# IOB-Inputs.net
KiCad netlist of a schematic drawn in EAGLE
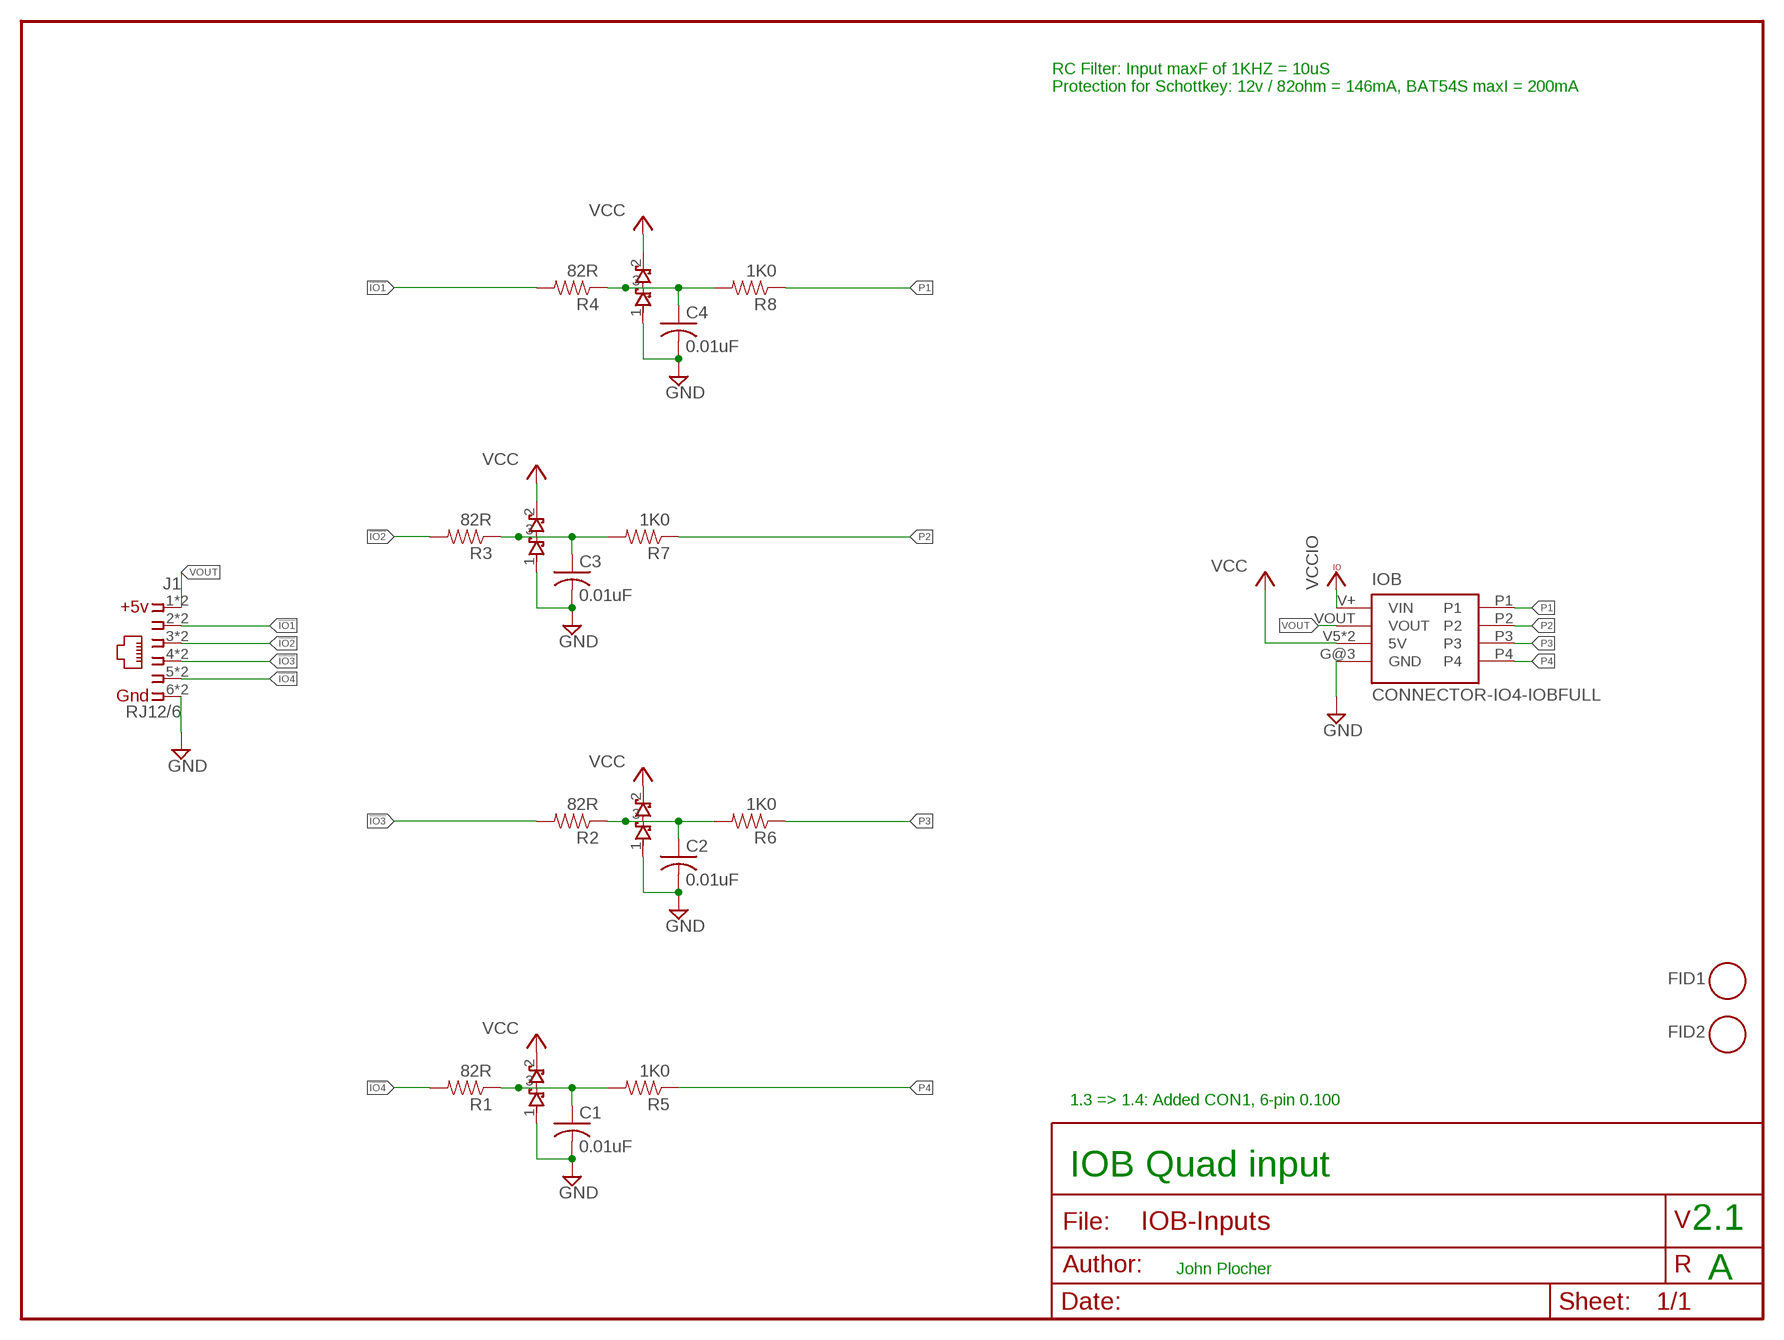
[diagram p0: schematic, sheet 1]

(export (version "E")
  (design (tool "Eeschema 10.0.6"))
  (components
    (comp (ref "C1")
      (value "0.01uF")
      (footprint "eagle-import:0603-CAP")
      (libsource (lib "eagle-import") (part "CAP0603"))
    )
    (comp (ref "C2")
      (value "0.01uF")
      (footprint "eagle-import:0603-CAP")
      (libsource (lib "eagle-import") (part "CAP0603"))
    )
    (comp (ref "C3")
      (value "0.01uF")
      (footprint "eagle-import:0603-CAP")
      (libsource (lib "eagle-import") (part "CAP0603"))
    )
    (comp (ref "C4")
      (value "0.01uF")
      (footprint "eagle-import:0603-CAP")
      (libsource (lib "eagle-import") (part "CAP0603"))
    )
    (comp (ref "D1")
      (value "BAT54S")
      (footprint "eagle-import:SOT23")
      (libsource (lib "eagle-import") (part "DIODE-BAT54S23"))
    )
    (comp (ref "D2")
      (value "BAT54S")
      (footprint "eagle-import:SOT23")
      (libsource (lib "eagle-import") (part "DIODE-BAT54S23"))
    )
    (comp (ref "D3")
      (value "BAT54S")
      (footprint "eagle-import:SOT23")
      (libsource (lib "eagle-import") (part "DIODE-BAT54S23"))
    )
    (comp (ref "D4")
      (value "BAT54S")
      (footprint "eagle-import:SOT23")
      (libsource (lib "eagle-import") (part "DIODE-BAT54S23"))
    )
    (comp (ref "FID1")
      (value "FIDUCIAL")
      (footprint "eagle-import:FIDUCIAL_1MM")
      (libsource (lib "eagle-import") (part "FIDUCIAL"))
    )
    (comp (ref "FID2")
      (value "FIDUCIAL")
      (footprint "eagle-import:FIDUCIAL_1MM")
      (libsource (lib "eagle-import") (part "FIDUCIAL"))
    )
    (comp (ref "IOB")
      (value "CONNECTOR-IO4-IOBFULL")
      (footprint "eagle-import:IO4-IOB")
      (libsource (lib "eagle-import") (part "CONNECTOR-IO4-IOBFULL"))
    )
    (comp (ref "J1")
      (value "RJ12/6")
      (footprint "eagle-import:RJ24-INVERTED-PINS")
      (libsource (lib "eagle-import") (part "CONNECTOR-IO4IPINS"))
    )
    (comp (ref "R1")
      (value "82R")
      (footprint "eagle-import:0805-RES")
      (libsource (lib "eagle-import") (part "R0805-RES"))
    )
    (comp (ref "R2")
      (value "82R")
      (footprint "eagle-import:0805-RES")
      (libsource (lib "eagle-import") (part "R0805-RES"))
    )
    (comp (ref "R3")
      (value "82R")
      (footprint "eagle-import:0805-RES")
      (libsource (lib "eagle-import") (part "R0805-RES"))
    )
    (comp (ref "R4")
      (value "82R")
      (footprint "eagle-import:0805-RES")
      (libsource (lib "eagle-import") (part "R0805-RES"))
    )
    (comp (ref "R5")
      (value "1K0")
      (footprint "eagle-import:0603-RES")
      (libsource (lib "eagle-import") (part "R0603-RES"))
    )
    (comp (ref "R6")
      (value "1K0")
      (footprint "eagle-import:0603-RES")
      (libsource (lib "eagle-import") (part "R0603-RES"))
    )
    (comp (ref "R7")
      (value "1K0")
      (footprint "eagle-import:0603-RES")
      (libsource (lib "eagle-import") (part "R0603-RES"))
    )
    (comp (ref "R8")
      (value "1K0")
      (footprint "eagle-import:0603-RES")
      (libsource (lib "eagle-import") (part "R0603-RES"))
    )
  )
  (nets
    (net (code "1") (name "/~{IO1}") (class "Default")
      (node (ref "J1") (pin "2") (pinfunction "2_2") (pintype "passive"))
      (node (ref "J1") (pin "2@1") (pinfunction "2_2@1") (pintype "passive"))
      (node (ref "R4") (pin "2") (pinfunction "2_2") (pintype "passive"))
    )
    (net (code "2") (name "/~{IO2}") (class "Default")
      (node (ref "J1") (pin "3") (pinfunction "3_3") (pintype "passive"))
      (node (ref "J1") (pin "3@1") (pinfunction "3_3@1") (pintype "passive"))
      (node (ref "R3") (pin "2") (pinfunction "2_2") (pintype "passive"))
    )
    (net (code "3") (name "/~{IO3}") (class "Default")
      (node (ref "J1") (pin "4") (pinfunction "4_4") (pintype "passive"))
      (node (ref "J1") (pin "4@1") (pinfunction "4_4@1") (pintype "passive"))
      (node (ref "R2") (pin "2") (pinfunction "2_2") (pintype "passive"))
    )
    (net (code "4") (name "/~{IO4}") (class "Default")
      (node (ref "J1") (pin "5") (pinfunction "5_5") (pintype "passive"))
      (node (ref "J1") (pin "5@1") (pinfunction "5_5@1") (pintype "passive"))
      (node (ref "R1") (pin "2") (pinfunction "2_2") (pintype "passive"))
    )
    (net (code "5") (name "GND") (class "Default")
      (node (ref "C1") (pin "2") (pinfunction "2_2") (pintype "passive"))
      (node (ref "C2") (pin "2") (pinfunction "2_2") (pintype "passive"))
      (node (ref "C3") (pin "2") (pinfunction "2_2") (pintype "passive"))
      (node (ref "C4") (pin "2") (pinfunction "2_2") (pintype "passive"))
      (node (ref "D1") (pin "1") (pinfunction "A1_1") (pintype "bidirectional"))
      (node (ref "D2") (pin "1") (pinfunction "A1_1") (pintype "bidirectional"))
      (node (ref "D3") (pin "1") (pinfunction "A1_1") (pintype "bidirectional"))
      (node (ref "D4") (pin "1") (pinfunction "A1_1") (pintype "bidirectional"))
      (node (ref "IOB") (pin "G@3") (pinfunction "GND_G@3") (pintype "power_in"))
      (node (ref "J1") (pin "6") (pinfunction "6_6") (pintype "power_in"))
      (node (ref "J1") (pin "6@1") (pinfunction "6_6@1") (pintype "power_in"))
    )
    (net (code "6") (name "Net-(D1-COM)") (class "Default")
      (node (ref "C1") (pin "1") (pinfunction "1_1") (pintype "passive"))
      (node (ref "D1") (pin "3") (pinfunction "COM_3") (pintype "bidirectional"))
      (node (ref "R1") (pin "1") (pinfunction "1_1") (pintype "passive"))
      (node (ref "R5") (pin "2") (pinfunction "2_2") (pintype "passive"))
    )
    (net (code "7") (name "Net-(D2-COM)") (class "Default")
      (node (ref "C2") (pin "1") (pinfunction "1_1") (pintype "passive"))
      (node (ref "D2") (pin "3") (pinfunction "COM_3") (pintype "bidirectional"))
      (node (ref "R2") (pin "1") (pinfunction "1_1") (pintype "passive"))
      (node (ref "R6") (pin "2") (pinfunction "2_2") (pintype "passive"))
    )
    (net (code "8") (name "Net-(D3-COM)") (class "Default")
      (node (ref "C3") (pin "1") (pinfunction "1_1") (pintype "passive"))
      (node (ref "D3") (pin "3") (pinfunction "COM_3") (pintype "bidirectional"))
      (node (ref "R3") (pin "1") (pinfunction "1_1") (pintype "passive"))
      (node (ref "R7") (pin "2") (pinfunction "2_2") (pintype "passive"))
    )
    (net (code "9") (name "Net-(D4-COM)") (class "Default")
      (node (ref "C4") (pin "1") (pinfunction "1_1") (pintype "passive"))
      (node (ref "D4") (pin "3") (pinfunction "COM_3") (pintype "bidirectional"))
      (node (ref "R4") (pin "1") (pinfunction "1_1") (pintype "passive"))
      (node (ref "R8") (pin "2") (pinfunction "2_2") (pintype "passive"))
    )
    (net (code "10") (name "P1") (class "Default")
      (node (ref "IOB") (pin "P1") (pinfunction "P1_P1") (pintype "bidirectional"))
      (node (ref "R8") (pin "1") (pinfunction "1_1") (pintype "passive"))
    )
    (net (code "11") (name "P2") (class "Default")
      (node (ref "IOB") (pin "P2") (pinfunction "P2_P2") (pintype "bidirectional"))
      (node (ref "R7") (pin "1") (pinfunction "1_1") (pintype "passive"))
    )
    (net (code "12") (name "P3") (class "Default")
      (node (ref "IOB") (pin "P3") (pinfunction "P3_P3") (pintype "bidirectional"))
      (node (ref "R6") (pin "1") (pinfunction "1_1") (pintype "passive"))
    )
    (net (code "13") (name "P4") (class "Default")
      (node (ref "IOB") (pin "P4") (pinfunction "P4_P4") (pintype "bidirectional"))
      (node (ref "R5") (pin "1") (pinfunction "1_1") (pintype "passive"))
    )
    (net (code "14") (name "VCC") (class "Default")
      (node (ref "D1") (pin "2") (pinfunction "C2_2") (pintype "bidirectional"))
      (node (ref "D2") (pin "2") (pinfunction "C2_2") (pintype "bidirectional"))
      (node (ref "D3") (pin "2") (pinfunction "C2_2") (pintype "bidirectional"))
      (node (ref "D4") (pin "2") (pinfunction "C2_2") (pintype "bidirectional"))
      (node (ref "IOB") (pin "V5") (pinfunction "5V_V5") (pintype "power_in"))
      (node (ref "IOB") (pin "V5@1") (pinfunction "5V_V5@1") (pintype "power_in"))
    )
    (net (code "15") (name "VCCIO") (class "Default")
      (node (ref "IOB") (pin "V+") (pinfunction "VIN_V+") (pintype "power_in"))
    )
    (net (code "16") (name "VOUT") (class "Default")
      (node (ref "IOB") (pin "VOUT") (pinfunction "VOUT_VOUT") (pintype "power_in"))
      (node (ref "J1") (pin "1") (pinfunction "1_1") (pintype "power_in"))
      (node (ref "J1") (pin "1@1") (pinfunction "1_1@1") (pintype "power_in"))
    )
  )
)
